# FPGA.net
KiCad netlist of a schematic drawn in Altium Designer
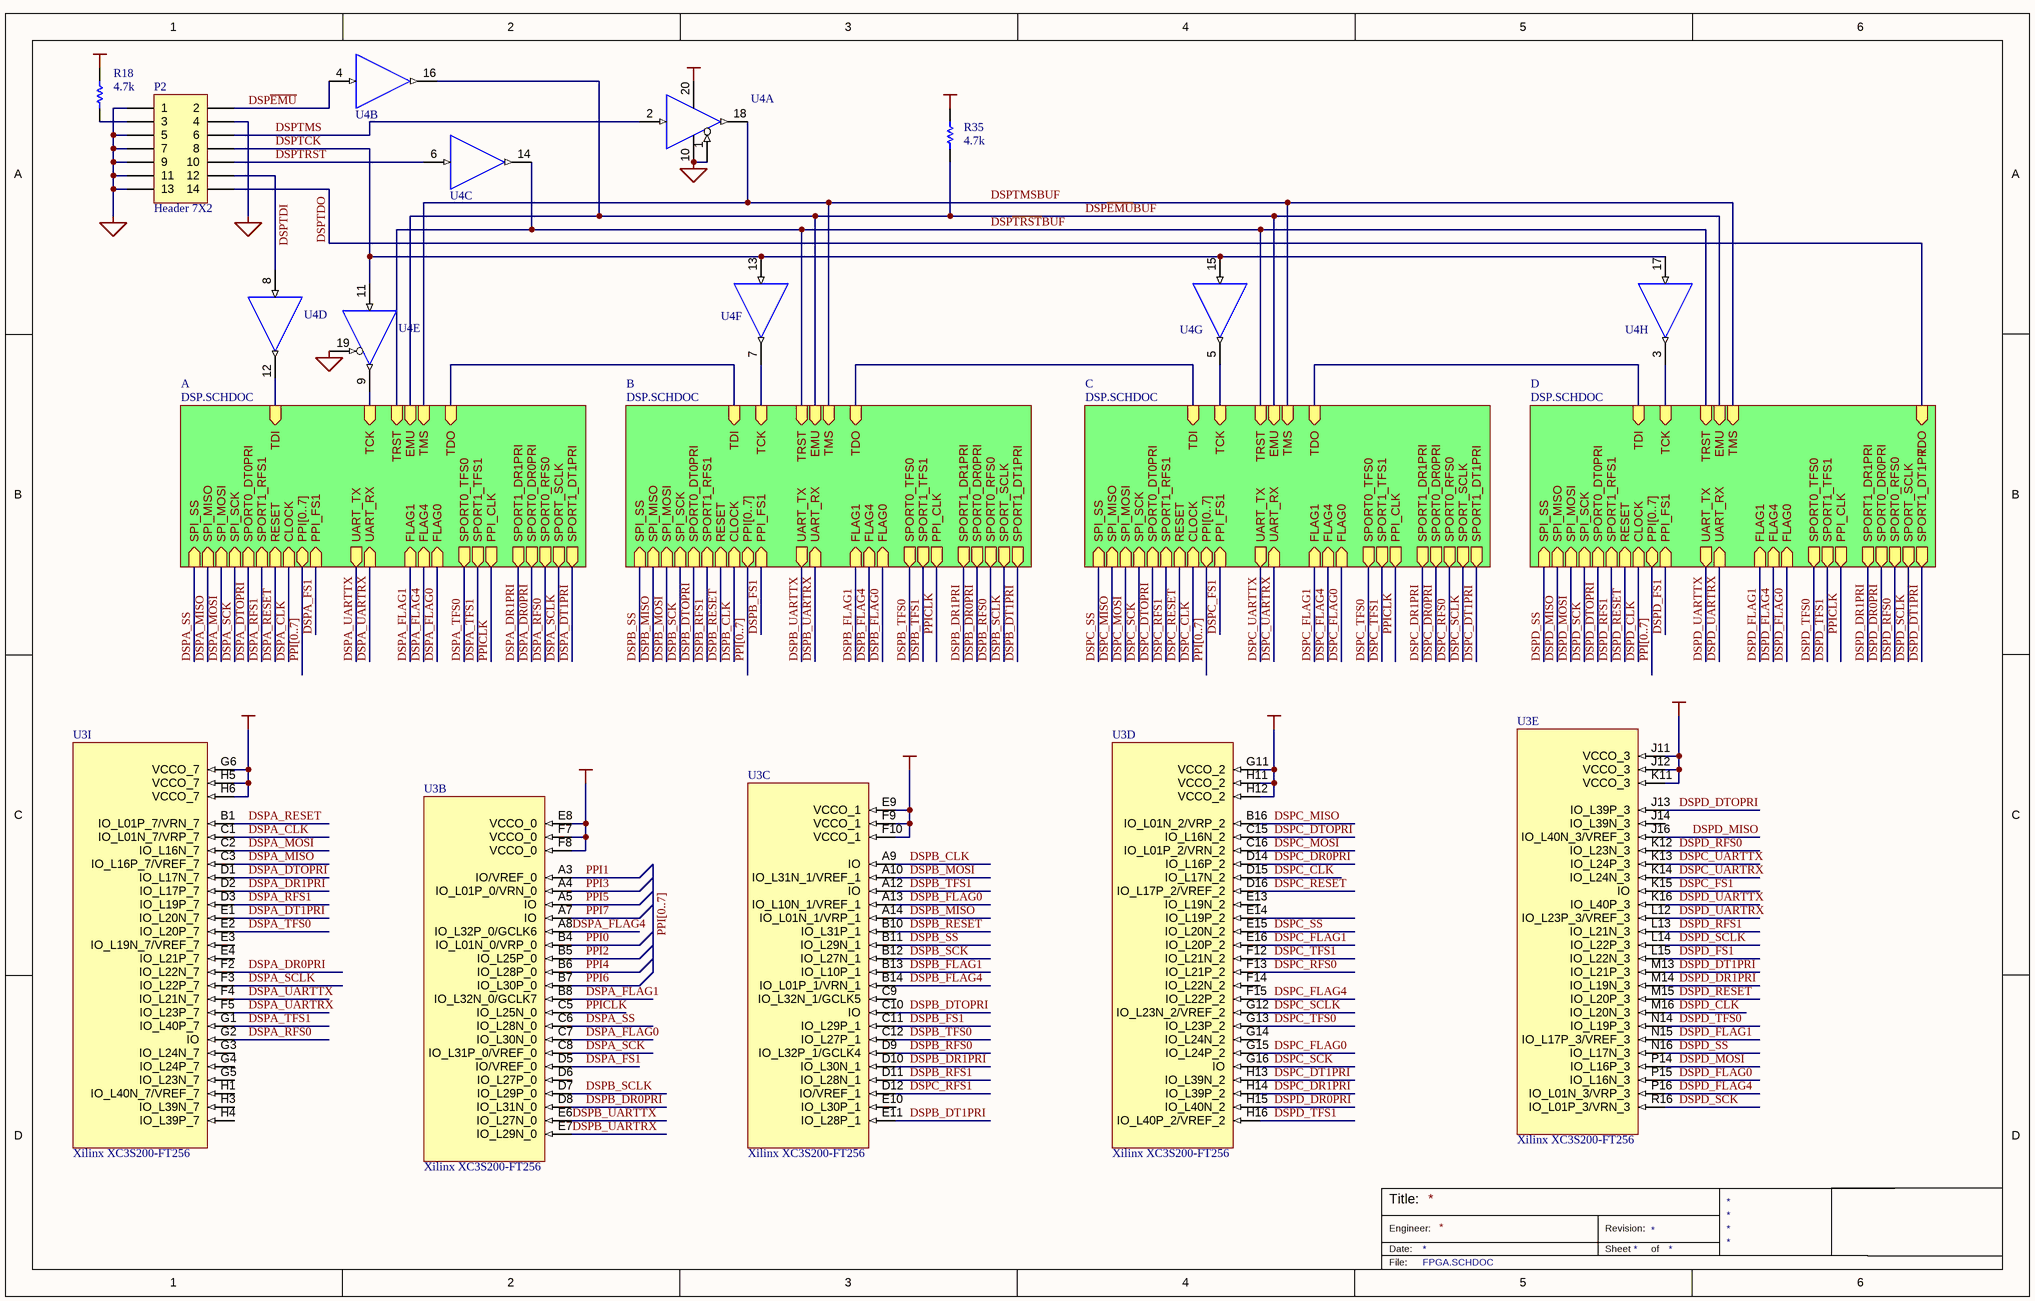
[diagram p0: FPGA.SCHDOC]

(export (version "E")
  (design (tool "Eeschema 10.0.6"))
  (components
    (comp (ref "P2")
      (value "Header 7X2")
      (footprint "HDR2X7")
      (description "Header, 7-Pin, Dual row")
      (fields (field (name "PUBLISHER") "Altium Limited"))
      (libsource (lib "Miscellaneous Connectors") (part "Header 7X2"))
    )
    (comp (ref "R18")
      (value "4.7k")
      (footprint "0603")
      (description "Standard Passive Resistor")
      (fields (field (name "TOLERANCE") "1%") (field (name "Comment") "RESISTOR"))
      (libsource (lib "parts") (part "RESISTOR"))
    )
    (comp (ref "R35")
      (value "4.7k")
      (footprint "0603")
      (description "Standard Passive Resistor")
      (fields (field (name "TOLERANCE") "1%") (field (name "Comment") "RESISTOR"))
      (libsource (lib "parts") (part "RESISTOR"))
    )
    (comp (ref "U3")
      (value "Xilinx XC3S200-FT256")
      (footprint "Xilinx FT256 BGA")
      (description "Xilinx Spartan-3 FPGA")
      (libsource (lib "parts") (part "XC3S200-FT256"))
    )
    (comp (ref "U4") (value "SN54LVTH244A") (footprint "RGY") (libsource (lib "parts") (part "SN54LVTH244A")))
  )
  (nets
    (net (code "1") (name "/DSPA_CLK") (class "Default")
      (node (ref "U3") (pin "C1") (pinfunction "IO_L01N_7/VRP_7_C1") (pintype "input"))
    )
    (net (code "2") (name "/DSPA_DR0PRI") (class "Default")
      (node (ref "U3") (pin "F2") (pinfunction "IO_L22N_7_F2") (pintype "input"))
    )
    (net (code "3") (name "/DSPA_DR1PRI") (class "Default")
      (node (ref "U3") (pin "D2") (pinfunction "IO_L17P_7_D2") (pintype "input"))
    )
    (net (code "4") (name "/DSPA_DT1PRI") (class "Default")
      (node (ref "U3") (pin "E1") (pinfunction "IO_L20N_7_E1") (pintype "input"))
    )
    (net (code "5") (name "/DSPA_DTOPRI") (class "Default")
      (node (ref "U3") (pin "D1") (pinfunction "IO_L17N_7_D1") (pintype "input"))
    )
    (net (code "6") (name "/DSPA_FLAG0") (class "Default")
      (node (ref "U3") (pin "C7") (pinfunction "IO_L30N_0_C7") (pintype "input"))
    )
    (net (code "7") (name "/DSPA_FLAG1") (class "Default")
      (node (ref "U3") (pin "B8") (pinfunction "IO_L32N_0/GCLK7_B8") (pintype "input"))
    )
    (net (code "8") (name "/DSPA_FLAG4") (class "Default")
      (node (ref "U3") (pin "A8") (pinfunction "IO_L32P_0/GCLK6_A8") (pintype "input"))
    )
    (net (code "9") (name "/DSPA_FS1") (class "Default")
      (node (ref "U3") (pin "D5") (pinfunction "IO/VREF_0_D5") (pintype "input"))
    )
    (net (code "10") (name "/DSPA_MISO") (class "Default")
      (node (ref "U3") (pin "C3") (pinfunction "IO_L16P_7/VREF_7_C3") (pintype "input"))
    )
    (net (code "11") (name "/DSPA_MOSI") (class "Default")
      (node (ref "U3") (pin "C2") (pinfunction "IO_L16N_7_C2") (pintype "input"))
    )
    (net (code "12") (name "/DSPA_RESET") (class "Default")
      (node (ref "U3") (pin "B1") (pinfunction "IO_L01P_7/VRN_7_B1") (pintype "input"))
    )
    (net (code "13") (name "/DSPA_RFS0") (class "Default")
      (node (ref "U3") (pin "G2") (pinfunction "IO_G2") (pintype "input"))
    )
    (net (code "14") (name "/DSPA_RFS1") (class "Default")
      (node (ref "U3") (pin "D3") (pinfunction "IO_L19P_7_D3") (pintype "input"))
    )
    (net (code "15") (name "/DSPA_SCK") (class "Default")
      (node (ref "U3") (pin "C8") (pinfunction "IO_L31P_0/VREF_0_C8") (pintype "input"))
    )
    (net (code "16") (name "/DSPA_SCLK") (class "Default")
      (node (ref "U3") (pin "F3") (pinfunction "IO_L22P_7_F3") (pintype "input"))
    )
    (net (code "17") (name "/DSPA_SS") (class "Default")
      (node (ref "U3") (pin "C6") (pinfunction "IO_L28N_0_C6") (pintype "input"))
    )
    (net (code "18") (name "/DSPA_TFS0") (class "Default")
      (node (ref "U3") (pin "E2") (pinfunction "IO_L20P_7_E2") (pintype "input"))
    )
    (net (code "19") (name "/DSPA_TFS1") (class "Default")
      (node (ref "U3") (pin "G1") (pinfunction "IO_L40P_7_G1") (pintype "input"))
    )
    (net (code "20") (name "/DSPA_UARTRX") (class "Default")
      (node (ref "U3") (pin "F5") (pinfunction "IO_L23P_7_F5") (pintype "input"))
    )
    (net (code "21") (name "/DSPA_UARTTX") (class "Default")
      (node (ref "U3") (pin "F4") (pinfunction "IO_L21N_7_F4") (pintype "input"))
    )
    (net (code "22") (name "/DSPB_CLK") (class "Default")
      (node (ref "U3") (pin "A9") (pinfunction "IO_A9") (pintype "input"))
    )
    (net (code "23") (name "/DSPB_DR0PRI") (class "Default")
      (node (ref "U3") (pin "D8") (pinfunction "IO_L31N_0_D8") (pintype "input"))
    )
    (net (code "24") (name "/DSPB_DR1PRI") (class "Default")
      (node (ref "U3") (pin "D10") (pinfunction "IO_L30N_1_D10") (pintype "input"))
    )
    (net (code "25") (name "/DSPB_DT1PRI") (class "Default")
      (node (ref "U3") (pin "E11") (pinfunction "IO_L28P_1_E11") (pintype "input"))
    )
    (net (code "26") (name "/DSPB_DTOPRI") (class "Default")
      (node (ref "U3") (pin "C10") (pinfunction "IO_C10") (pintype "input"))
    )
    (net (code "27") (name "/DSPB_FLAG0") (class "Default")
      (node (ref "U3") (pin "A13") (pinfunction "IO_L10N_1/VREF_1_A13") (pintype "input"))
    )
    (net (code "28") (name "/DSPB_FLAG1") (class "Default")
      (node (ref "U3") (pin "B13") (pinfunction "IO_L10P_1_B13") (pintype "input"))
    )
    (net (code "29") (name "/DSPB_FLAG4") (class "Default")
      (node (ref "U3") (pin "B14") (pinfunction "IO_L01P_1/VRN_1_B14") (pintype "input"))
    )
    (net (code "30") (name "/DSPB_FS1") (class "Default")
      (node (ref "U3") (pin "C11") (pinfunction "IO_L29P_1_C11") (pintype "input"))
    )
    (net (code "31") (name "/DSPB_MISO") (class "Default")
      (node (ref "U3") (pin "A14") (pinfunction "IO_L01N_1/VRP_1_A14") (pintype "input"))
    )
    (net (code "32") (name "/DSPB_MOSI") (class "Default")
      (node (ref "U3") (pin "A10") (pinfunction "IO_L31N_1/VREF_1_A10") (pintype "input"))
    )
    (net (code "33") (name "/DSPB_RESET") (class "Default")
      (node (ref "U3") (pin "B10") (pinfunction "IO_L31P_1_B10") (pintype "input"))
    )
    (net (code "34") (name "/DSPB_RFS0") (class "Default")
      (node (ref "U3") (pin "D9") (pinfunction "IO_L32P_1/GCLK4_D9") (pintype "input"))
    )
    (net (code "35") (name "/DSPB_RFS1") (class "Default")
      (node (ref "U3") (pin "D11") (pinfunction "IO_L28N_1_D11") (pintype "input"))
    )
    (net (code "36") (name "/DSPB_SCK") (class "Default")
      (node (ref "U3") (pin "B12") (pinfunction "IO_L27N_1_B12") (pintype "input"))
    )
    (net (code "37") (name "/DSPB_SCLK") (class "Default")
      (node (ref "U3") (pin "D7") (pinfunction "IO_L29P_0_D7") (pintype "input"))
    )
    (net (code "38") (name "/DSPB_SS") (class "Default")
      (node (ref "U3") (pin "B11") (pinfunction "IO_L29N_1_B11") (pintype "input"))
    )
    (net (code "39") (name "/DSPB_TFS0") (class "Default")
      (node (ref "U3") (pin "C12") (pinfunction "IO_L27P_1_C12") (pintype "input"))
    )
    (net (code "40") (name "/DSPB_TFS1") (class "Default")
      (node (ref "U3") (pin "A12") (pinfunction "IO_A12") (pintype "input"))
    )
    (net (code "41") (name "/DSPB_UARTRX") (class "Default")
      (node (ref "U3") (pin "E7") (pinfunction "IO_L29N_0_E7") (pintype "input"))
    )
    (net (code "42") (name "/DSPB_UARTTX") (class "Default")
      (node (ref "U3") (pin "E6") (pinfunction "IO_L27N_0_E6") (pintype "input"))
    )
    (net (code "43") (name "/DSPC_CLK") (class "Default")
      (node (ref "U3") (pin "D15") (pinfunction "IO_L17N_2_D15") (pintype "input"))
    )
    (net (code "44") (name "/DSPC_DR0PRI") (class "Default")
      (node (ref "U3") (pin "D14") (pinfunction "IO_L16P_2_D14") (pintype "input"))
    )
    (net (code "45") (name "/DSPC_DR1PRI") (class "Default")
      (node (ref "U3") (pin "H14") (pinfunction "IO_L39P_2_H14") (pintype "input"))
    )
    (net (code "46") (name "/DSPC_DT1PRI") (class "Default")
      (node (ref "U3") (pin "H13") (pinfunction "IO_L39N_2_H13") (pintype "input"))
    )
    (net (code "47") (name "/DSPC_DTOPRI") (class "Default")
      (node (ref "U3") (pin "C15") (pinfunction "IO_L16N_2_C15") (pintype "input"))
    )
    (net (code "48") (name "/DSPC_FLAG0") (class "Default")
      (node (ref "U3") (pin "G15") (pinfunction "IO_L24P_2_G15") (pintype "input"))
    )
    (net (code "49") (name "/DSPC_FLAG1") (class "Default")
      (node (ref "U3") (pin "E16") (pinfunction "IO_L20P_2_E16") (pintype "input"))
    )
    (net (code "50") (name "/DSPC_FLAG4") (class "Default")
      (node (ref "U3") (pin "F15") (pinfunction "IO_L22P_2_F15") (pintype "input"))
    )
    (net (code "51") (name "/DSPC_FS1") (class "Default")
      (node (ref "U3") (pin "K15") (pinfunction "IO_K15") (pintype "input"))
    )
    (net (code "52") (name "/DSPC_MISO") (class "Default")
      (node (ref "U3") (pin "B16") (pinfunction "IO_L01N_2/VRP_2_B16") (pintype "input"))
    )
    (net (code "53") (name "/DSPC_MOSI") (class "Default")
      (node (ref "U3") (pin "C16") (pinfunction "IO_L01P_2/VRN_2_C16") (pintype "input"))
    )
    (net (code "54") (name "/DSPC_RESET") (class "Default")
      (node (ref "U3") (pin "D16") (pinfunction "IO_L17P_2/VREF_2_D16") (pintype "input"))
    )
    (net (code "55") (name "/DSPC_RFS0") (class "Default")
      (node (ref "U3") (pin "F13") (pinfunction "IO_L21P_2_F13") (pintype "input"))
    )
    (net (code "56") (name "/DSPC_RFS1") (class "Default")
      (node (ref "U3") (pin "D12") (pinfunction "IO/VREF_1_D12") (pintype "input"))
    )
    (net (code "57") (name "/DSPC_SCK") (class "Default")
      (node (ref "U3") (pin "G16") (pinfunction "IO_G16") (pintype "input"))
    )
    (net (code "58") (name "/DSPC_SCLK") (class "Default")
      (node (ref "U3") (pin "G12") (pinfunction "IO_L23N_2/VREF_2_G12") (pintype "input"))
    )
    (net (code "59") (name "/DSPC_SS") (class "Default")
      (node (ref "U3") (pin "E15") (pinfunction "IO_L20N_2_E15") (pintype "input"))
    )
    (net (code "60") (name "/DSPC_TFS0") (class "Default")
      (node (ref "U3") (pin "G13") (pinfunction "IO_L23P_2_G13") (pintype "input"))
    )
    (net (code "61") (name "/DSPC_TFS1") (class "Default")
      (node (ref "U3") (pin "F12") (pinfunction "IO_L21N_2_F12") (pintype "input"))
    )
    (net (code "62") (name "/DSPC_UARTRX") (class "Default")
      (node (ref "U3") (pin "K14") (pinfunction "IO_L24N_3_K14") (pintype "input"))
    )
    (net (code "63") (name "/DSPC_UARTTX") (class "Default")
      (node (ref "U3") (pin "K13") (pinfunction "IO_L24P_3_K13") (pintype "input"))
    )
    (net (code "64") (name "/DSPD_CLK") (class "Default")
      (node (ref "U3") (pin "M16") (pinfunction "IO_L20N_3_M16") (pintype "input"))
    )
    (net (code "65") (name "/DSPD_DR0PRI") (class "Default")
      (node (ref "U3") (pin "H15") (pinfunction "IO_L40N_2_H15") (pintype "input"))
    )
    (net (code "66") (name "/DSPD_DR1PRI") (class "Default")
      (node (ref "U3") (pin "M14") (pinfunction "IO_L19N_3_M14") (pintype "input"))
    )
    (net (code "67") (name "/DSPD_DT1PRI") (class "Default")
      (node (ref "U3") (pin "M13") (pinfunction "IO_L21P_3_M13") (pintype "input"))
    )
    (net (code "68") (name "/DSPD_DTOPRI") (class "Default")
      (node (ref "U3") (pin "J13") (pinfunction "IO_L39P_3_J13") (pintype "input"))
    )
    (net (code "69") (name "/DSPD_FLAG0") (class "Default")
      (node (ref "U3") (pin "P15") (pinfunction "IO_L16N_3_P15") (pintype "input"))
    )
    (net (code "70") (name "/DSPD_FLAG1") (class "Default")
      (node (ref "U3") (pin "N15") (pinfunction "IO_L17P_3/VREF_3_N15") (pintype "input"))
    )
    (net (code "71") (name "/DSPD_FLAG4") (class "Default")
      (node (ref "U3") (pin "P16") (pinfunction "IO_L01N_3/VRP_3_P16") (pintype "input"))
    )
    (net (code "72") (name "/DSPD_FS1") (class "Default")
      (node (ref "U3") (pin "L15") (pinfunction "IO_L22N_3_L15") (pintype "input"))
    )
    (net (code "73") (name "/DSPD_MISO") (class "Default")
      (node (ref "U3") (pin "J16") (pinfunction "IO_L40N_3/VREF_3_J16") (pintype "input"))
    )
    (net (code "74") (name "/DSPD_MOSI") (class "Default")
      (node (ref "U3") (pin "P14") (pinfunction "IO_L16P_3_P14") (pintype "input"))
    )
    (net (code "75") (name "/DSPD_RESET") (class "Default")
      (node (ref "U3") (pin "M15") (pinfunction "IO_L20P_3_M15") (pintype "input"))
    )
    (net (code "76") (name "/DSPD_RFS0") (class "Default")
      (node (ref "U3") (pin "K12") (pinfunction "IO_L23N_3_K12") (pintype "input"))
    )
    (net (code "77") (name "/DSPD_RFS1") (class "Default")
      (node (ref "U3") (pin "L13") (pinfunction "IO_L21N_3_L13") (pintype "input"))
    )
    (net (code "78") (name "/DSPD_SCK") (class "Default")
      (node (ref "U3") (pin "R16") (pinfunction "IO_L01P_3/VRN_3_R16") (pintype "input"))
    )
    (net (code "79") (name "/DSPD_SCLK") (class "Default")
      (node (ref "U3") (pin "L14") (pinfunction "IO_L22P_3_L14") (pintype "input"))
    )
    (net (code "80") (name "/DSPD_SS") (class "Default")
      (node (ref "U3") (pin "N16") (pinfunction "IO_L17N_3_N16") (pintype "input"))
    )
    (net (code "81") (name "/DSPD_TFS0") (class "Default")
      (node (ref "U3") (pin "N14") (pinfunction "IO_L19P_3_N14") (pintype "input"))
    )
    (net (code "82") (name "/DSPD_TFS1") (class "Default")
      (node (ref "U3") (pin "H16") (pinfunction "IO_L40P_2/VREF_2_H16") (pintype "input"))
    )
    (net (code "83") (name "/DSPD_UARTRX") (class "Default")
      (node (ref "U3") (pin "L12") (pinfunction "IO_L23P_3/VREF_3_L12") (pintype "input"))
    )
    (net (code "84") (name "/DSPD_UARTTX") (class "Default")
      (node (ref "U3") (pin "K16") (pinfunction "IO_L40P_3_K16") (pintype "input"))
    )
    (net (code "85") (name "/DSPTCK") (class "Default")
      (node (ref "P2") (pin "8") (pinfunction "8_8") (pintype "passive"))
      (node (ref "U4") (pin "11") (pinfunction "IN_11") (pintype "input"))
      (node (ref "U4") (pin "13") (pinfunction "IN_13") (pintype "input"))
      (node (ref "U4") (pin "15") (pinfunction "IN_15") (pintype "input"))
      (node (ref "U4") (pin "17") (pinfunction "IN_17") (pintype "input"))
    )
    (net (code "86") (name "/DSPTDI") (class "Default")
      (node (ref "P2") (pin "12") (pinfunction "12_12") (pintype "passive"))
      (node (ref "U4") (pin "8") (pinfunction "IN_8") (pintype "input"))
    )
    (net (code "87") (name "/DSPTDO") (class "Default")
      (node (ref "P2") (pin "14") (pinfunction "14_14") (pintype "passive"))
    )
    (net (code "88") (name "/DSPTMS") (class "Default")
      (node (ref "P2") (pin "6") (pinfunction "6_6") (pintype "passive"))
      (node (ref "U4") (pin "2") (pinfunction "IN_2") (pintype "input"))
    )
    (net (code "89") (name "/DSPTMSBUF") (class "Default")
      (node (ref "U4") (pin "18") (pinfunction "OUT_18") (pintype "output"))
    )
    (net (code "90") (name "/DSP~{EMU}") (class "Default")
      (node (ref "P2") (pin "2") (pinfunction "2_2") (pintype "passive"))
      (node (ref "U4") (pin "4") (pinfunction "IN_4") (pintype "input"))
    )
    (net (code "91") (name "/DSP~{EMU}BUF") (class "Default")
      (node (ref "R35") (pin "1") (pintype "passive"))
      (node (ref "U4") (pin "16") (pinfunction "OUT_16") (pintype "output"))
    )
    (net (code "92") (name "/DSP~{TRST}") (class "Default")
      (node (ref "P2") (pin "10") (pinfunction "10_10") (pintype "passive"))
      (node (ref "U4") (pin "6") (pinfunction "IN_6") (pintype "input"))
    )
    (net (code "93") (name "/DSP~{TRST}BUF") (class "Default")
      (node (ref "U4") (pin "14") (pinfunction "OUT_14") (pintype "output"))
    )
    (net (code "94") (name "/PPI0") (class "Default")
      (node (ref "U3") (pin "B4") (pinfunction "IO_L01N_0/VRP_0_B4") (pintype "input"))
    )
    (net (code "95") (name "/PPI1") (class "Default")
      (node (ref "U3") (pin "A3") (pinfunction "IO/VREF_0_A3") (pintype "input"))
    )
    (net (code "96") (name "/PPI2") (class "Default")
      (node (ref "U3") (pin "B5") (pinfunction "IO_L25P_0_B5") (pintype "input"))
    )
    (net (code "97") (name "/PPI3") (class "Default")
      (node (ref "U3") (pin "A4") (pinfunction "IO_L01P_0/VRN_0_A4") (pintype "input"))
    )
    (net (code "98") (name "/PPI4") (class "Default")
      (node (ref "U3") (pin "B6") (pinfunction "IO_L28P_0_B6") (pintype "input"))
    )
    (net (code "99") (name "/PPI5") (class "Default")
      (node (ref "U3") (pin "A5") (pinfunction "IO_A5") (pintype "input"))
    )
    (net (code "100") (name "/PPI6") (class "Default")
      (node (ref "U3") (pin "B7") (pinfunction "IO_L30P_0_B7") (pintype "input"))
    )
    (net (code "101") (name "/PPI7") (class "Default")
      (node (ref "U3") (pin "A7") (pinfunction "IO_A7") (pintype "input"))
    )
    (net (code "102") (name "/PPICLK") (class "Default")
      (node (ref "U3") (pin "C5") (pinfunction "IO_L25N_0_C5") (pintype "input"))
    )
    (net (code "104") (name "/TCK") (class "Default")
      (node (ref "U4") (pin "5") (pinfunction "OUT_5") (pintype "output"))
    )
    (net (code "105") (name "/TCK_1") (class "Default")
      (node (ref "U4") (pin "3") (pinfunction "OUT_3") (pintype "output"))
    )
    (net (code "106") (name "/TCK_2") (class "Default")
      (node (ref "U4") (pin "9") (pinfunction "OUT_9") (pintype "output"))
    )
    (net (code "107") (name "/TCK_3") (class "Default")
      (node (ref "U4") (pin "7") (pinfunction "OUT_7") (pintype "output"))
    )
    (net (code "110") (name "/TDI_2") (class "Default")
      (node (ref "U4") (pin "12") (pinfunction "OUT_12") (pintype "output"))
    )
    (net (code "112") (name "GND") (class "Default")
      (node (ref "P2") (pin "1") (pinfunction "1_1") (pintype "passive"))
      (node (ref "P2") (pin "11") (pinfunction "11_11") (pintype "passive"))
      (node (ref "P2") (pin "13") (pinfunction "13_13") (pintype "passive"))
      (node (ref "P2") (pin "4") (pinfunction "4_4") (pintype "passive"))
      (node (ref "P2") (pin "5") (pinfunction "5_5") (pintype "passive"))
      (node (ref "P2") (pin "7") (pinfunction "7_7") (pintype "passive"))
      (node (ref "P2") (pin "9") (pinfunction "9_9") (pintype "passive"))
      (node (ref "U4") (pin "1") (pinfunction "~{1OE}_1") (pintype "input"))
      (node (ref "U4") (pin "10") (pinfunction "GND_10") (pintype "power_in"))
      (node (ref "U4") (pin "19") (pinfunction "~{2OE}_19") (pintype "input"))
    )
    (net (code "113") (name "Net-(P2-Pad3)") (class "Default")
      (node (ref "P2") (pin "3") (pinfunction "3_3") (pintype "passive"))
      (node (ref "R18") (pin "1") (pintype "passive"))
    )
    (net (code "114") (name "VCC") (class "Default")
      (node (ref "R18") (pin "2") (pintype "passive"))
      (node (ref "R35") (pin "2") (pintype "passive"))
      (node (ref "U3") (pin "E8") (pinfunction "VCCO_0_E8") (pintype "input"))
      (node (ref "U3") (pin "E9") (pinfunction "VCCO_1_E9") (pintype "input"))
      (node (ref "U3") (pin "F10") (pinfunction "VCCO_1_F10") (pintype "input"))
      (node (ref "U3") (pin "F7") (pinfunction "VCCO_0_F7") (pintype "input"))
      (node (ref "U3") (pin "F8") (pinfunction "VCCO_0_F8") (pintype "input"))
      (node (ref "U3") (pin "F9") (pinfunction "VCCO_1_F9") (pintype "input"))
      (node (ref "U3") (pin "G11") (pinfunction "VCCO_2_G11") (pintype "input"))
      (node (ref "U3") (pin "G6") (pinfunction "VCCO_7_G6") (pintype "input"))
      (node (ref "U3") (pin "H11") (pinfunction "VCCO_2_H11") (pintype "input"))
      (node (ref "U3") (pin "H12") (pinfunction "VCCO_2_H12") (pintype "input"))
      (node (ref "U3") (pin "H5") (pinfunction "VCCO_7_H5") (pintype "input"))
      (node (ref "U3") (pin "H6") (pinfunction "VCCO_7_H6") (pintype "input"))
      (node (ref "U3") (pin "J11") (pinfunction "VCCO_3_J11") (pintype "input"))
      (node (ref "U3") (pin "J12") (pinfunction "VCCO_3_J12") (pintype "input"))
      (node (ref "U3") (pin "K11") (pinfunction "VCCO_3_K11") (pintype "input"))
      (node (ref "U4") (pin "20") (pinfunction "VCC_20") (pintype "power_in"))
    )
    (net (code "115") (name "unconnected-(U3B-IO_L27P_0-PadD6)") (class "Default")
      (node (ref "U3") (pin "D6") (pinfunction "IO_L27P_0_D6") (pintype "input"))
    )
    (net (code "116") (name "unconnected-(U3C-IO_L30P_1-PadE10)") (class "Default")
      (node (ref "U3") (pin "E10") (pinfunction "IO_L30P_1_E10") (pintype "input"))
    )
    (net (code "117") (name "unconnected-(U3C-IO_L32N_1{slash}GCLK5-PadC9)") (class "Default")
      (node (ref "U3") (pin "C9") (pinfunction "IO_L32N_1/GCLK5_C9") (pintype "input"))
    )
    (net (code "118") (name "unconnected-(U3D-IO_L19N_2-PadE13)") (class "Default")
      (node (ref "U3") (pin "E13") (pinfunction "IO_L19N_2_E13") (pintype "input"))
    )
    (net (code "119") (name "unconnected-(U3D-IO_L19P_2-PadE14)") (class "Default")
      (node (ref "U3") (pin "E14") (pinfunction "IO_L19P_2_E14") (pintype "input"))
    )
    (net (code "120") (name "unconnected-(U3D-IO_L22N_2-PadF14)") (class "Default")
      (node (ref "U3") (pin "F14") (pinfunction "IO_L22N_2_F14") (pintype "input"))
    )
    (net (code "121") (name "unconnected-(U3D-IO_L24N_2-PadG14)") (class "Default")
      (node (ref "U3") (pin "G14") (pinfunction "IO_L24N_2_G14") (pintype "input"))
    )
    (net (code "122") (name "unconnected-(U3E-IO_L39N_3-PadJ14)") (class "Default")
      (node (ref "U3") (pin "J14") (pinfunction "IO_L39N_3_J14") (pintype "input"))
    )
    (net (code "123") (name "unconnected-(U3I-IO_L19N_7{slash}VREF_7-PadE3)") (class "Default")
      (node (ref "U3") (pin "E3") (pinfunction "IO_L19N_7/VREF_7_E3") (pintype "input"))
    )
    (net (code "124") (name "unconnected-(U3I-IO_L21P_7-PadE4)") (class "Default")
      (node (ref "U3") (pin "E4") (pinfunction "IO_L21P_7_E4") (pintype "input"))
    )
    (net (code "125") (name "unconnected-(U3I-IO_L23N_7-PadG5)") (class "Default")
      (node (ref "U3") (pin "G5") (pinfunction "IO_L23N_7_G5") (pintype "input"))
    )
    (net (code "126") (name "unconnected-(U3I-IO_L24N_7-PadG3)") (class "Default")
      (node (ref "U3") (pin "G3") (pinfunction "IO_L24N_7_G3") (pintype "input"))
    )
    (net (code "127") (name "unconnected-(U3I-IO_L24P_7-PadG4)") (class "Default")
      (node (ref "U3") (pin "G4") (pinfunction "IO_L24P_7_G4") (pintype "input"))
    )
    (net (code "128") (name "unconnected-(U3I-IO_L39N_7-PadH3)") (class "Default")
      (node (ref "U3") (pin "H3") (pinfunction "IO_L39N_7_H3") (pintype "input"))
    )
    (net (code "129") (name "unconnected-(U3I-IO_L39P_7-PadH4)") (class "Default")
      (node (ref "U3") (pin "H4") (pinfunction "IO_L39P_7_H4") (pintype "input"))
    )
    (net (code "130") (name "unconnected-(U3I-IO_L40N_7{slash}VREF_7-PadH1)") (class "Default")
      (node (ref "U3") (pin "H1") (pinfunction "IO_L40N_7/VREF_7_H1") (pintype "input"))
    )
  )
)
